# k64_breakout.net
KiCad netlist of a schematic drawn in EAGLE
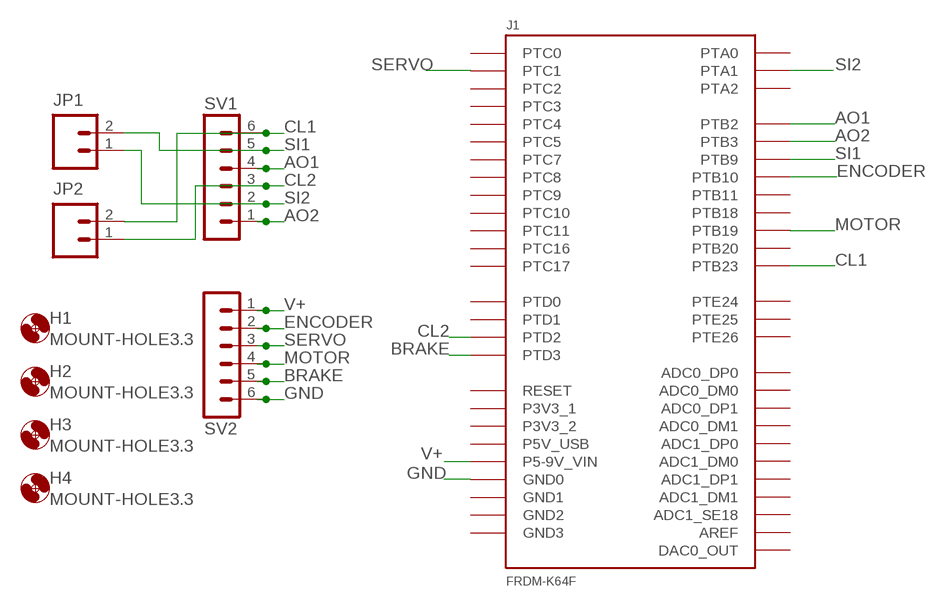
[diagram p0: schematic, sheet 1]

(export (version "E")
  (design (tool "Eeschema 10.0.6"))
  (components
    (comp (ref "H1")
      (value "MOUNT-HOLE3.3")
      (footprint "eagle-import:3,3")
      (libsource (lib "eagle-import") (part "MOUNT-HOLE3.3"))
    )
    (comp (ref "H2")
      (value "MOUNT-HOLE3.3")
      (footprint "eagle-import:3,3")
      (libsource (lib "eagle-import") (part "MOUNT-HOLE3.3"))
    )
    (comp (ref "H3")
      (value "MOUNT-HOLE3.3")
      (footprint "eagle-import:3,3")
      (libsource (lib "eagle-import") (part "MOUNT-HOLE3.3"))
    )
    (comp (ref "H4")
      (value "MOUNT-HOLE3.3")
      (footprint "eagle-import:3,3")
      (libsource (lib "eagle-import") (part "MOUNT-HOLE3.3"))
    )
    (comp (ref "J1")
      (value "FRDM-K64F")
      (footprint "eagle-import:FRDM-K64F")
      (libsource (lib "eagle-import") (part "FRDM-K64F"))
    )
    (comp (ref "JP1")
      (value "M02PTH")
      (footprint "eagle-import:1X02")
      (libsource (lib "eagle-import") (part "M02PTH"))
    )
    (comp (ref "JP2")
      (value "M02PTH")
      (footprint "eagle-import:1X02")
      (libsource (lib "eagle-import") (part "M02PTH"))
    )
    (comp (ref "SV1")
      (value "MA06-1")
      (footprint "eagle-import:MA06-1")
      (libsource (lib "eagle-import") (part "MA06-1"))
    )
    (comp (ref "SV2")
      (value "MA06-1")
      (footprint "eagle-import:MA06-1")
      (libsource (lib "eagle-import") (part "MA06-1"))
    )
  )
  (nets
    (net (code "1") (name "/AO1") (class "Default")
      (node (ref "J1") (pin "J4-2") (pinfunction "PTB2_J4-2") (pintype "bidirectional"))
      (node (ref "SV1") (pin "4") (pinfunction "4_4") (pintype "passive"))
    )
    (net (code "2") (name "/AO2") (class "Default")
      (node (ref "J1") (pin "J4-4") (pinfunction "PTB3_J4-4") (pintype "bidirectional"))
      (node (ref "SV1") (pin "1") (pinfunction "1_1") (pintype "passive"))
    )
    (net (code "3") (name "/BRAKE") (class "Default")
      (node (ref "J1") (pin "J2-10") (pinfunction "PTD3_J2-10") (pintype "bidirectional"))
      (node (ref "SV2") (pin "5") (pinfunction "5_5") (pintype "passive"))
    )
    (net (code "4") (name "/CL1") (class "Default")
      (node (ref "J1") (pin "J1-10") (pinfunction "PTB23_J1-10") (pintype "bidirectional"))
      (node (ref "JP2") (pin "2") (pinfunction "2_2") (pintype "passive"))
      (node (ref "SV1") (pin "6") (pinfunction "6_6") (pintype "passive"))
    )
    (net (code "5") (name "/CL2") (class "Default")
      (node (ref "J1") (pin "J2-8") (pinfunction "PTD2_J2-8") (pintype "bidirectional"))
      (node (ref "JP2") (pin "1") (pinfunction "1_1") (pintype "passive"))
      (node (ref "SV1") (pin "3") (pinfunction "3_3") (pintype "passive"))
    )
    (net (code "6") (name "/ENCODER") (class "Default")
      (node (ref "J1") (pin "J4-6") (pinfunction "PTB10_J4-6") (pintype "bidirectional"))
      (node (ref "SV2") (pin "2") (pinfunction "2_2") (pintype "passive"))
    )
    (net (code "7") (name "/GND") (class "Default")
      (node (ref "J1") (pin "J2-3") (pinfunction "GND0_J2-3") (pintype "bidirectional"))
      (node (ref "SV2") (pin "6") (pinfunction "6_6") (pintype "passive"))
    )
    (net (code "8") (name "/MOTOR") (class "Default")
      (node (ref "J1") (pin "J1-3") (pinfunction "PTB19_J1-3") (pintype "bidirectional"))
      (node (ref "SV2") (pin "4") (pinfunction "4_4") (pintype "passive"))
    )
    (net (code "9") (name "/SERVO") (class "Default")
      (node (ref "J1") (pin "J1-5") (pinfunction "PTC1_J1-5") (pintype "bidirectional"))
      (node (ref "SV2") (pin "3") (pinfunction "3_3") (pintype "passive"))
    )
    (net (code "10") (name "/SI1") (class "Default")
      (node (ref "J1") (pin "J1-6") (pinfunction "PTB9_J1-6") (pintype "bidirectional"))
      (node (ref "JP1") (pin "2") (pinfunction "2_2") (pintype "passive"))
      (node (ref "SV1") (pin "5") (pinfunction "5_5") (pintype "passive"))
    )
    (net (code "11") (name "/SI2") (class "Default")
      (node (ref "J1") (pin "J1-8") (pinfunction "PTA1_J1-8") (pintype "bidirectional"))
      (node (ref "JP1") (pin "1") (pinfunction "1_1") (pintype "passive"))
      (node (ref "SV1") (pin "2") (pinfunction "2_2") (pintype "passive"))
    )
    (net (code "12") (name "/V+") (class "Default")
      (node (ref "J1") (pin "J3-16") (pinfunction "P5-9V_VIN_J3-16") (pintype "bidirectional"))
      (node (ref "SV2") (pin "1") (pinfunction "1_1") (pintype "passive"))
    )
    (net (code "13") (name "unconnected-(J1-ADC0_DM0-PadJ2-7)") (class "Default")
      (node (ref "J1") (pin "J2-7") (pinfunction "ADC0_DM0_J2-7") (pintype "bidirectional"))
    )
    (net (code "14") (name "unconnected-(J1-ADC0_DM1-PadJ4-3)") (class "Default")
      (node (ref "J1") (pin "J4-3") (pinfunction "ADC0_DM1_J4-3") (pintype "bidirectional"))
    )
    (net (code "15") (name "unconnected-(J1-ADC0_DP0-PadJ2-5)") (class "Default")
      (node (ref "J1") (pin "J2-5") (pinfunction "ADC0_DP0_J2-5") (pintype "bidirectional"))
    )
    (net (code "16") (name "unconnected-(J1-ADC0_DP1-PadJ4-1)") (class "Default")
      (node (ref "J1") (pin "J4-1") (pinfunction "ADC0_DP1_J4-1") (pintype "bidirectional"))
    )
    (net (code "17") (name "unconnected-(J1-ADC1_DM0-PadJ2-13)") (class "Default")
      (node (ref "J1") (pin "J2-13") (pinfunction "ADC1_DM0_J2-13") (pintype "bidirectional"))
    )
    (net (code "18") (name "unconnected-(J1-ADC1_DM1-PadJ4-7)") (class "Default")
      (node (ref "J1") (pin "J4-7") (pinfunction "ADC1_DM1_J4-7") (pintype "bidirectional"))
    )
    (net (code "19") (name "unconnected-(J1-ADC1_DP0-PadJ2-11)") (class "Default")
      (node (ref "J1") (pin "J2-11") (pinfunction "ADC1_DP0_J2-11") (pintype "bidirectional"))
    )
    (net (code "20") (name "unconnected-(J1-ADC1_DP1-PadJ4-5)") (class "Default")
      (node (ref "J1") (pin "J4-5") (pinfunction "ADC1_DP1_J4-5") (pintype "bidirectional"))
    )
    (net (code "21") (name "unconnected-(J1-ADC1_SE18-PadJ2-17)") (class "Default")
      (node (ref "J1") (pin "J2-17") (pinfunction "ADC1_SE18_J2-17") (pintype "bidirectional"))
    )
    (net (code "22") (name "unconnected-(J1-AREF-PadJ2-16)") (class "Default")
      (node (ref "J1") (pin "J2-16") (pinfunction "AREF_J2-16") (pintype "bidirectional"))
    )
    (net (code "23") (name "unconnected-(J1-DAC0_OUT-PadJ4-11)") (class "Default")
      (node (ref "J1") (pin "J4-11") (pinfunction "DAC0_OUT_J4-11") (pintype "bidirectional"))
    )
    (net (code "24") (name "unconnected-(J1-GND1-PadJ2-14)") (class "Default")
      (node (ref "J1") (pin "J2-14") (pinfunction "GND1_J2-14") (pintype "bidirectional"))
    )
    (net (code "25") (name "unconnected-(J1-GND2-PadJ3-12)") (class "Default")
      (node (ref "J1") (pin "J3-12") (pinfunction "GND2_J3-12") (pintype "bidirectional"))
    )
    (net (code "26") (name "unconnected-(J1-GND3-PadJ3-14)") (class "Default")
      (node (ref "J1") (pin "J3-14") (pinfunction "GND3_J3-14") (pintype "bidirectional"))
    )
    (net (code "27") (name "unconnected-(J1-P3V3_1-PadJ3-4)") (class "Default")
      (node (ref "J1") (pin "J3-4") (pinfunction "P3V3_1_J3-4") (pintype "bidirectional"))
    )
    (net (code "28") (name "unconnected-(J1-P3V3_2-PadJ3-8)") (class "Default")
      (node (ref "J1") (pin "J3-8") (pinfunction "P3V3_2_J3-8") (pintype "bidirectional"))
    )
    (net (code "29") (name "unconnected-(J1-P5V_USB-PadJ3-10)") (class "Default")
      (node (ref "J1") (pin "J3-10") (pinfunction "P5V_USB_J3-10") (pintype "bidirectional"))
    )
    (net (code "30") (name "unconnected-(J1-PTA0-PadJ2-2)") (class "Default")
      (node (ref "J1") (pin "J2-2") (pinfunction "PTA0_J2-2") (pintype "bidirectional"))
    )
    (net (code "31") (name "unconnected-(J1-PTA2-PadJ1-12)") (class "Default")
      (node (ref "J1") (pin "J1-12") (pinfunction "PTA2_J1-12") (pintype "bidirectional"))
    )
    (net (code "32") (name "unconnected-(J1-PTB11-PadJ4-8)") (class "Default")
      (node (ref "J1") (pin "J4-8") (pinfunction "PTB11_J4-8") (pintype "bidirectional"))
    )
    (net (code "33") (name "unconnected-(J1-PTB18-PadJ1-1)") (class "Default")
      (node (ref "J1") (pin "J1-1") (pinfunction "PTB18_J1-1") (pintype "bidirectional"))
    )
    (net (code "34") (name "unconnected-(J1-PTB20-PadJ4-9)") (class "Default")
      (node (ref "J1") (pin "J4-9") (pinfunction "PTB20_J4-9") (pintype "bidirectional"))
    )
    (net (code "35") (name "unconnected-(J1-PTC0-PadJ1-11)") (class "Default")
      (node (ref "J1") (pin "J1-11") (pinfunction "PTC0_J1-11") (pintype "bidirectional"))
    )
    (net (code "36") (name "unconnected-(J1-PTC2-PadJ1-14)") (class "Default")
      (node (ref "J1") (pin "J1-14") (pinfunction "PTC2_J1-14") (pintype "bidirectional"))
    )
    (net (code "37") (name "unconnected-(J1-PTC3-PadJ1-16)") (class "Default")
      (node (ref "J1") (pin "J1-16") (pinfunction "PTC3_J1-16") (pintype "bidirectional"))
    )
    (net (code "38") (name "unconnected-(J1-PTC4-PadJ2-4)") (class "Default")
      (node (ref "J1") (pin "J2-4") (pinfunction "PTC4_J2-4") (pintype "bidirectional"))
    )
    (net (code "39") (name "unconnected-(J1-PTC5-PadJ1-15)") (class "Default")
      (node (ref "J1") (pin "J1-15") (pinfunction "PTC5_J1-15") (pintype "bidirectional"))
    )
    (net (code "40") (name "unconnected-(J1-PTC7-PadJ1-13)") (class "Default")
      (node (ref "J1") (pin "J1-13") (pinfunction "PTC7_J1-13") (pintype "bidirectional"))
    )
    (net (code "41") (name "unconnected-(J1-PTC8-PadJ1-7)") (class "Default")
      (node (ref "J1") (pin "J1-7") (pinfunction "PTC8_J1-7") (pintype "bidirectional"))
    )
    (net (code "42") (name "unconnected-(J1-PTC9-PadJ1-9)") (class "Default")
      (node (ref "J1") (pin "J1-9") (pinfunction "PTC9_J1-9") (pintype "bidirectional"))
    )
    (net (code "43") (name "unconnected-(J1-PTC10-PadJ4-12)") (class "Default")
      (node (ref "J1") (pin "J4-12") (pinfunction "PTC10_J4-12") (pintype "bidirectional"))
    )
    (net (code "44") (name "unconnected-(J1-PTC11-PadJ4-10)") (class "Default")
      (node (ref "J1") (pin "J4-10") (pinfunction "PTC11_J4-10") (pintype "bidirectional"))
    )
    (net (code "45") (name "unconnected-(J1-PTC16-PadJ1-2)") (class "Default")
      (node (ref "J1") (pin "J1-2") (pinfunction "PTC16_J1-2") (pintype "bidirectional"))
    )
    (net (code "46") (name "unconnected-(J1-PTC17-PadJ1-4)") (class "Default")
      (node (ref "J1") (pin "J1-4") (pinfunction "PTC17_J1-4") (pintype "bidirectional"))
    )
    (net (code "47") (name "unconnected-(J1-PTD0-PadJ2-6)") (class "Default")
      (node (ref "J1") (pin "J2-6") (pinfunction "PTD0_J2-6") (pintype "bidirectional"))
    )
    (net (code "48") (name "unconnected-(J1-PTD1-PadJ2-12)") (class "Default")
      (node (ref "J1") (pin "J2-12") (pinfunction "PTD1_J2-12") (pintype "bidirectional"))
    )
    (net (code "49") (name "unconnected-(J1-PTE24-PadJ2-20)") (class "Default")
      (node (ref "J1") (pin "J2-20") (pinfunction "PTE24_J2-20") (pintype "bidirectional"))
    )
    (net (code "50") (name "unconnected-(J1-PTE25-PadJ2-18)") (class "Default")
      (node (ref "J1") (pin "J2-18") (pinfunction "PTE25_J2-18") (pintype "bidirectional"))
    )
    (net (code "51") (name "unconnected-(J1-PTE26-PadJ2-1)") (class "Default")
      (node (ref "J1") (pin "J2-1") (pinfunction "PTE26_J2-1") (pintype "bidirectional"))
    )
    (net (code "52") (name "unconnected-(J1-RESET-PadJ3-6)") (class "Default")
      (node (ref "J1") (pin "J3-6") (pinfunction "RESET_J3-6") (pintype "bidirectional"))
    )
  )
)
